# Sheet2.net
KiCad netlist of a schematic drawn in Altium Designer
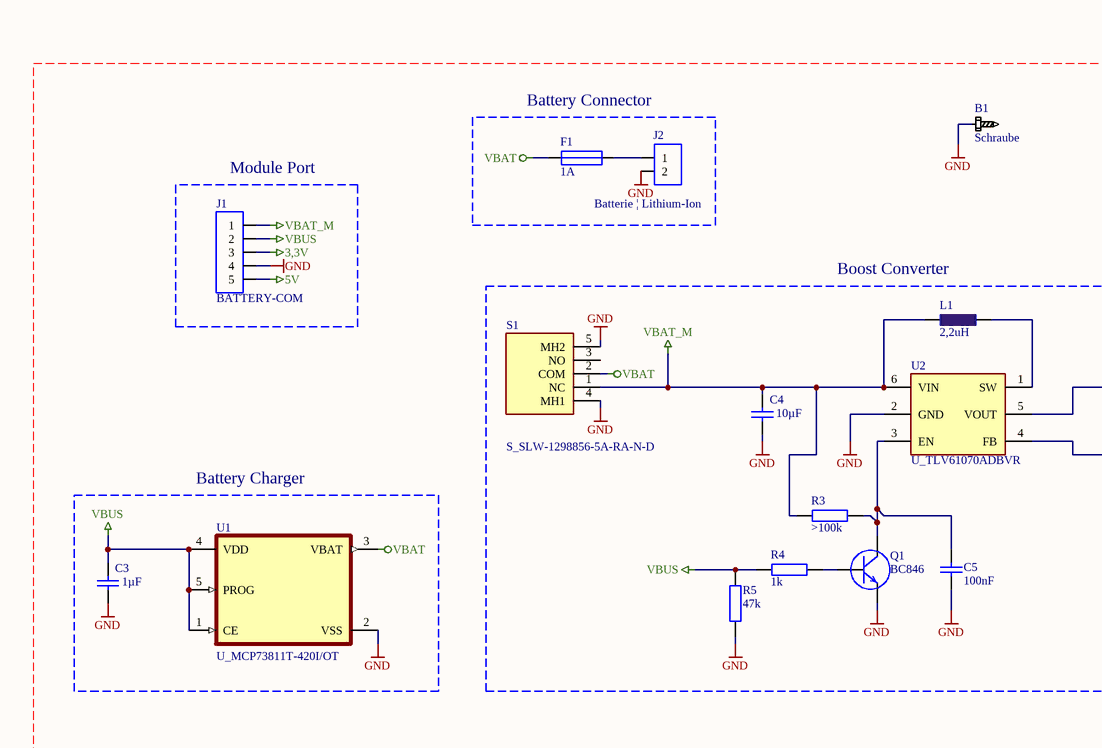
[diagram p0: Sheet2.SchDoc, top left]
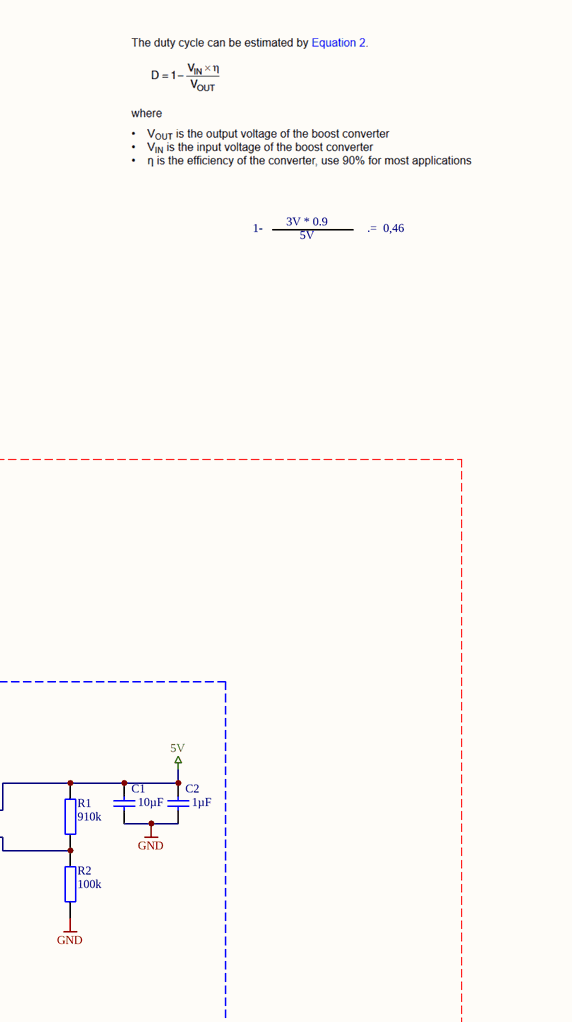
[diagram p1: Sheet2.SchDoc, top right]
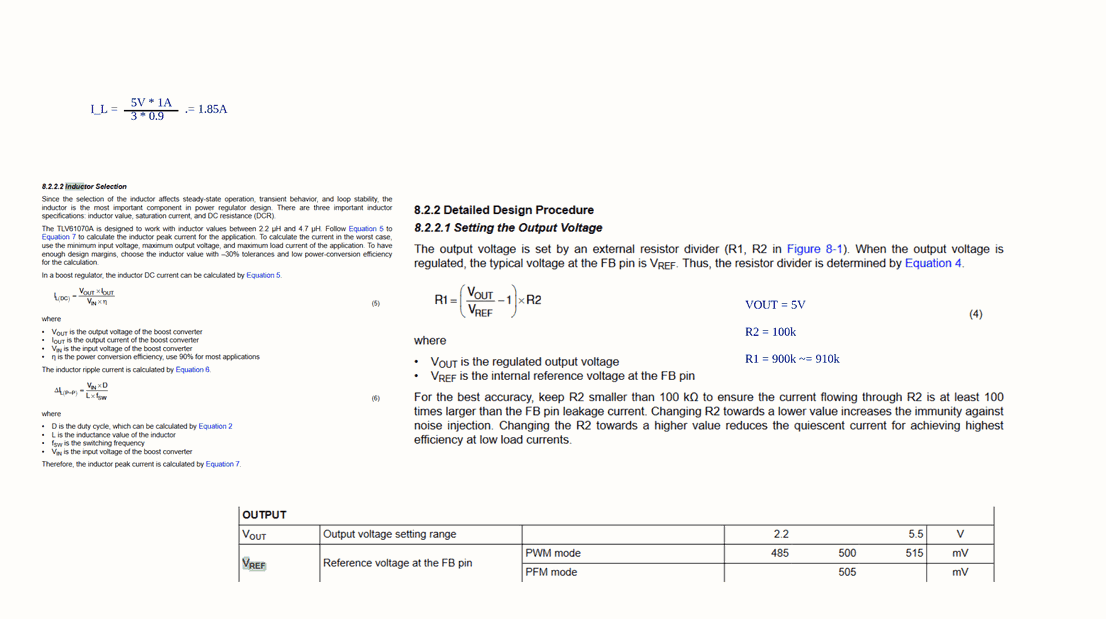
[diagram p2: Sheet2.SchDoc, bottom left]
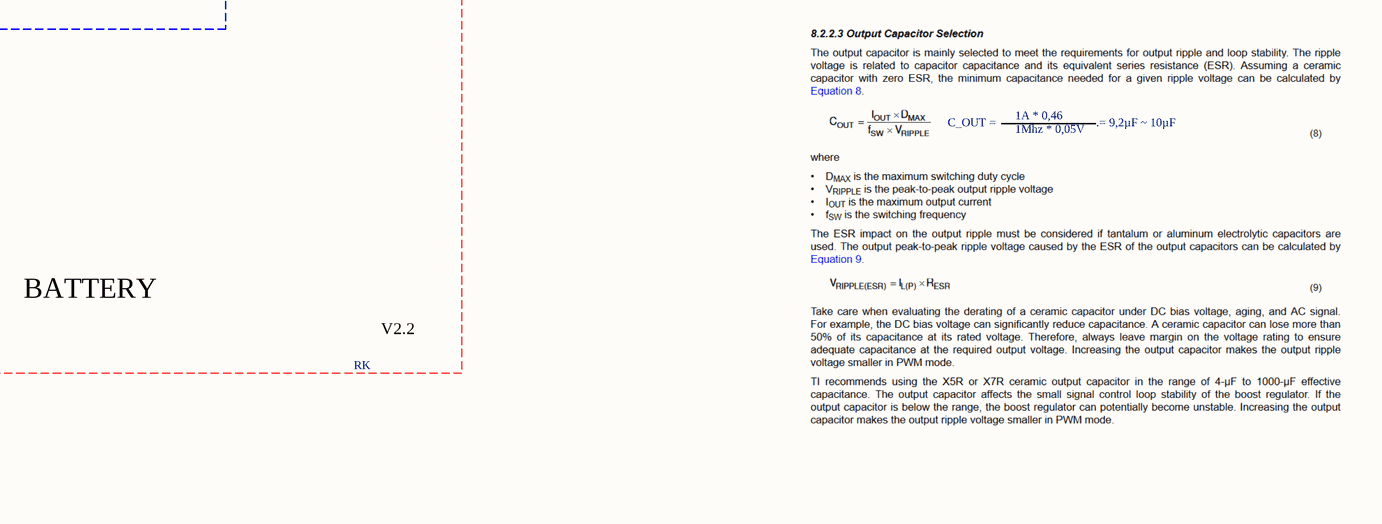
[diagram p3: Sheet2.SchDoc, bottom right]

(export (version "E")
  (design (tool "Eeschema 10.0.6"))
  (components
    (comp (ref "B1")
      (value "Schraube")
      (footprint "B_Schraube-M3 PAD")
      (description "Schraubenloch für M3 Schrauben")
      (libsource (lib "SCHLIB-PCSB_5.1.3") (part "B_Schraube"))
    )
    (comp (ref "C1")
      (value "10µF")
      (footprint "C_SMD_0805")
      (description "Kondensator SMD Universal, Keramik, Folie, usw.")
      (libsource (lib "SCHLIB-PCSB_5.1.3") (part "C_SMD_KO"))
    )
    (comp (ref "C2")
      (value "1µF")
      (footprint "C_SMD_0805")
      (description "Kondensator SMD Universal, Keramik, Folie, usw.")
      (libsource (lib "SCHLIB-PCSB_5.1.3") (part "C_SMD_KO"))
    )
    (comp (ref "C3")
      (value "1µF")
      (footprint "C_SMD_0805")
      (description "Kondensator SMD Universal, Keramik, Folie, usw.")
      (libsource (lib "SCHLIB-PCSB_5.1.3") (part "C_SMD_KO"))
    )
    (comp (ref "C4")
      (value "10µF")
      (footprint "C_SMD_0805")
      (description "Kondensator SMD Universal, Keramik, Folie, usw.")
      (libsource (lib "SCHLIB-PCSB_5.1.3") (part "C_SMD_KO"))
    )
    (comp (ref "C5")
      (value "100nF")
      (footprint "C_SMD_0603")
      (description "Kondensator SMD Universal, Keramik, Folie, usw.")
      (libsource (lib "SCHLIB-PCSB_5.1.3") (part "C_SMD_KO"))
    )
    (comp (ref "F1")
      (value "1A")
      (footprint "F_OMF63_Schurtner")
      (description "Sicherung")
      (libsource (lib "SCHLIB-PCSB_5.1.3") (part "F_THT_Fuse"))
    )
    (comp (ref "J1")
      (value "BATTERY-COM")
      (footprint "SIP-5")
      (description "Stecker")
      (libsource (lib "SCHLIB-PCSB_5.1.3") (part "J_THT_CON5"))
    )
    (comp (ref "J2")
      (value "Batterie ¦ Lithium-Ion")
      (footprint "J_THT_Printklemme 2x")
      (description "Stecker")
      (libsource (lib "SCHLIB-PCSB_5.1.3") (part "J_THT_CON2"))
    )
    (comp (ref "L1")
      (value "2,2uH")
      (footprint "L_SMD_74438357100")
      (description "Spule SMD")
      (libsource (lib "SCHLIB-PCSB_5.1.3") (part "L_SMD_Spule"))
    )
    (comp (ref "Q1")
      (value "BC846")
      (footprint "SOT-23-3_BC846")
      (description "NPN Transistor")
      (libsource (lib "SCHLIB-PCSB_5.1.3") (part "Q_SMD_NPN"))
    )
    (comp (ref "R1")
      (value "910k")
      (footprint "R_SMD_0805")
      (description "Widerstand SMD")
      (libsource (lib "SCHLIB-PCSB_5.1.3") (part "R_SMD_Widerstand"))
    )
    (comp (ref "R2")
      (value "100k")
      (footprint "R_SMD_0805")
      (description "Widerstand SMD")
      (libsource (lib "SCHLIB-PCSB_5.1.3") (part "R_SMD_Widerstand"))
    )
    (comp (ref "R3")
      (value ">100k")
      (footprint "R_SMD_0805")
      (description "Widerstand SMD")
      (libsource (lib "SCHLIB-PCSB_5.1.3") (part "R_SMD_Widerstand"))
    )
    (comp (ref "R4")
      (value "1k")
      (footprint "R_SMD_0805")
      (description "Widerstand SMD")
      (libsource (lib "SCHLIB-PCSB_5.1.3") (part "R_SMD_Widerstand"))
    )
    (comp (ref "R5")
      (value "47k")
      (footprint "R_SMD_0805")
      (description "Widerstand SMD")
      (libsource (lib "SCHLIB-PCSB_5.1.3") (part "R_SMD_Widerstand"))
    )
    (comp (ref "S1")
      (value "S_SLW-1298856-5A-RA-N-D")
      (footprint "SLW12988565ARAND")
      (description "Switch")
      (fields (field (name "MANUFACTURER_PART_NUMBER") "SLW-1298856-5A-RA-N-D"))
      (libsource (lib "SCHLIB-PCSB_5.1.3") (part "S_SLW-1298856-5A-RA-N-D"))
    )
    (comp (ref "U1")
      (value "U_MCP73811T-420I/OT")
      (footprint "SOT95P280X145-5N")
      (description "Charger IC Lithium Ion/Polymer SOT-23-5")
      (fields (field (name "MF") "Microchip") (field (name "MP") "MCP73811T-420I/OT"))
      (libsource (lib "SCHLIB-PCSB_5.1.3") (part "U_MCP73811T-420I/OT"))
    )
    (comp (ref "U2")
      (value "U_TLV61070ADBVR")
      (footprint "SOT23-6")
      (description "Integrated Circuit, Boost converter: Input 0.5 - 5.5V \r\nOutput 2.2 - 5.5V")
      (fields
        (field (name "MANUFACTURER_PART_NUMBER") "TLV61070ADBVR")
        (field (name "MOUSER PART NUMBER") "595-TLV61070ADBVR")
      )
      (libsource (lib "SCHLIB-PCSB_5.1.3") (part "U_TLV61070ADBVR"))
    )
  )
  (nets
    (net (code "1") (name "3,3V") (class "Default")
      (node (ref "J1") (pin "3") (pinfunction "3_3") (pintype "passive"))
    )
    (net (code "2") (name "5V") (class "Default")
      (node (ref "C1") (pin "1") (pintype "passive"))
      (node (ref "C2") (pin "1") (pintype "passive"))
      (node (ref "J1") (pin "5") (pinfunction "5_5") (pintype "passive"))
      (node (ref "R1") (pin "2") (pintype "passive"))
      (node (ref "U2") (pin "5") (pinfunction "VOUT_5") (pintype "passive"))
    )
    (net (code "3") (name "GND") (class "Default")
      (node (ref "B1") (pin "1") (pinfunction "PAD_1") (pintype "passive"))
      (node (ref "C1") (pin "2") (pintype "passive"))
      (node (ref "C2") (pin "2") (pintype "passive"))
      (node (ref "C3") (pin "2") (pintype "passive"))
      (node (ref "C4") (pin "2") (pintype "passive"))
      (node (ref "C5") (pin "2") (pintype "passive"))
      (node (ref "J1") (pin "4") (pinfunction "4_4") (pintype "passive"))
      (node (ref "J2") (pin "2") (pinfunction "2_2") (pintype "passive"))
      (node (ref "Q1") (pin "E") (pinfunction "E_E") (pintype "passive"))
      (node (ref "R2") (pin "1") (pintype "passive"))
      (node (ref "R5") (pin "1") (pintype "passive"))
      (node (ref "S1") (pin "4") (pinfunction "MH1_4") (pintype "passive"))
      (node (ref "S1") (pin "5") (pinfunction "MH2_5") (pintype "passive"))
      (node (ref "U1") (pin "2") (pinfunction "VSS_2") (pintype "power_in"))
      (node (ref "U2") (pin "2") (pinfunction "GND_2") (pintype "passive"))
    )
    (net (code "4") (name "Net-(F1-Pad2)") (class "Default")
      (node (ref "F1") (pin "2") (pinfunction "2_2") (pintype "passive"))
      (node (ref "J2") (pin "1") (pinfunction "1_1") (pintype "passive"))
    )
    (net (code "5") (name "Net-(Q1-PadB)") (class "Default")
      (node (ref "Q1") (pin "B") (pinfunction "B_B") (pintype "passive"))
      (node (ref "R4") (pin "2") (pintype "passive"))
    )
    (net (code "6") (name "Net-(U2-EN)") (class "Default")
      (node (ref "C5") (pin "1") (pintype "passive"))
      (node (ref "Q1") (pin "C") (pinfunction "C_C") (pintype "passive"))
      (node (ref "R3") (pin "2") (pintype "passive"))
      (node (ref "U2") (pin "3") (pinfunction "EN_3") (pintype "passive"))
    )
    (net (code "7") (name "Net-(U2-FB)") (class "Default")
      (node (ref "R1") (pin "1") (pintype "passive"))
      (node (ref "R2") (pin "2") (pintype "passive"))
      (node (ref "U2") (pin "4") (pinfunction "FB_4") (pintype "passive"))
    )
    (net (code "8") (name "Net-(U2-SW)") (class "Default")
      (node (ref "L1") (pin "1") (pintype "passive"))
      (node (ref "U2") (pin "1") (pinfunction "SW_1") (pintype "passive"))
    )
    (net (code "9") (name "VBAT") (class "Default")
      (node (ref "F1") (pin "1") (pintype "passive"))
      (node (ref "S1") (pin "2") (pinfunction "COM_2") (pintype "passive"))
      (node (ref "U1") (pin "3") (pinfunction "VBAT_3") (pintype "output"))
    )
    (net (code "10") (name "VBAT_M") (class "Default")
      (node (ref "C4") (pin "1") (pintype "passive"))
      (node (ref "J1") (pin "1") (pinfunction "1_1") (pintype "passive"))
      (node (ref "L1") (pin "2") (pintype "passive"))
      (node (ref "R3") (pin "1") (pintype "passive"))
      (node (ref "S1") (pin "1") (pinfunction "NC_1") (pintype "passive"))
      (node (ref "U2") (pin "6") (pinfunction "VIN_6") (pintype "passive"))
    )
    (net (code "11") (name "VBUS") (class "Default")
      (node (ref "C3") (pin "1") (pintype "passive"))
      (node (ref "J1") (pin "2") (pinfunction "2_2") (pintype "passive"))
      (node (ref "R4") (pin "1") (pintype "passive"))
      (node (ref "R5") (pin "2") (pintype "passive"))
      (node (ref "U1") (pin "1") (pinfunction "CE_1") (pintype "input"))
      (node (ref "U1") (pin "4") (pinfunction "VDD_4") (pintype "power_in"))
      (node (ref "U1") (pin "5") (pinfunction "PROG_5") (pintype "input"))
    )
    (net (code "12") (name "unconnected-(S1-NO-Pad3)") (class "Default")
      (node (ref "S1") (pin "3") (pinfunction "NO_3") (pintype "passive"))
    )
  )
)
